# Shift_register_shematic.net
KiCad netlist of a schematic drawn in EAGLE
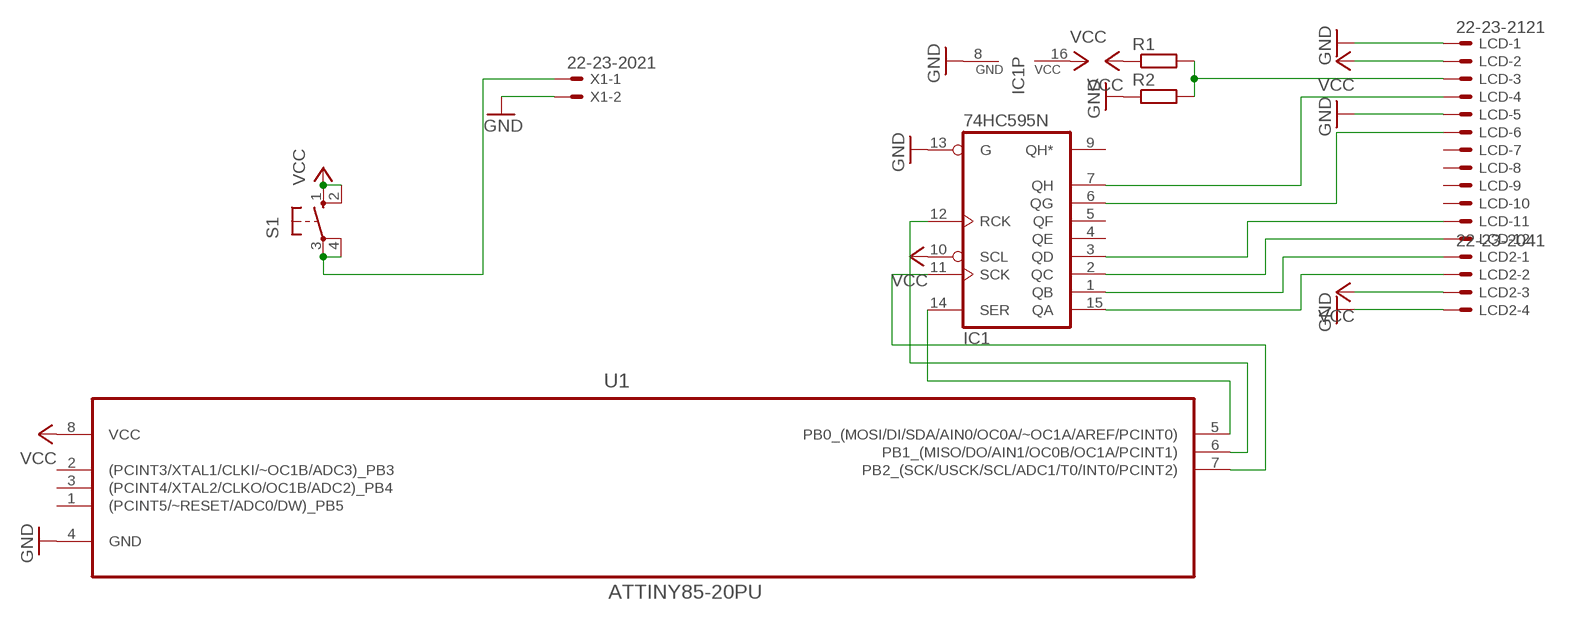
[diagram p0: schematic, sheet 1]

(export (version "E")
  (design (tool "Eeschema 10.0.6"))
  (components
    (comp (ref "IC1")
      (value "74HC595N")
      (footprint "eagle-import:DIL16")
      (libsource (lib "eagle-import") (part "74595NHC"))
    )
    (comp (ref "LCD")
      (value "22-23-2121")
      (footprint "eagle-import:22-23-2121")
      (fields (field (name "MF") "MOLEX"))
      (libsource (lib "eagle-import") (part "22-23-2121"))
    )
    (comp (ref "LCD2")
      (value "22-23-2041")
      (footprint "eagle-import:22-23-2041")
      (fields (field (name "MF") "MOLEX"))
      (libsource (lib "eagle-import") (part "22-23-2041"))
    )
    (comp (ref "R1")
      (value "R-EU_0207/10")
      (footprint "eagle-import:0207_10")
      (libsource (lib "eagle-import") (part "R-EU_0207/10"))
    )
    (comp (ref "R2")
      (value "R-EU_0207/10")
      (footprint "eagle-import:0207_10")
      (libsource (lib "eagle-import") (part "R-EU_0207/10"))
    )
    (comp (ref "S1")
      (value "40-XX")
      (footprint "eagle-import:B3F-40XX")
      (fields (field (name "MF") "OMRON COMPONENTS USA") (field (name "MPN") "B3F-4000"))
      (libsource (lib "eagle-import") (part "40-XX"))
    )
    (comp (ref "U1")
      (value "ATTINY85-20PU")
      (footprint "eagle-import:DIP254P762X533-8")
      (libsource (lib "eagle-import") (part "ATTINY85-20PU"))
    )
    (comp (ref "X1")
      (value "22-23-2021")
      (footprint "eagle-import:22-23-2021")
      (fields (field (name "MF") "MOLEX"))
      (libsource (lib "eagle-import") (part "22-23-2021"))
    )
  )
  (nets
    (net (code "1") (name "GND") (class "Default")
      (node (ref "IC1") (pin "13") (pinfunction "G_13") (pintype "input"))
      (node (ref "IC1") (pin "8") (pinfunction "GND_8") (pintype "power_in"))
      (node (ref "LCD") (pin "1") (pinfunction "S_1") (pintype "passive"))
      (node (ref "LCD") (pin "5") (pinfunction "S_5") (pintype "passive"))
      (node (ref "LCD2") (pin "4") (pinfunction "S_4") (pintype "passive"))
      (node (ref "R2") (pin "1") (pinfunction "1_1") (pintype "passive"))
      (node (ref "U1") (pin "4") (pinfunction "GND_4") (pintype "passive"))
      (node (ref "X1") (pin "2") (pinfunction "S_2") (pintype "passive"))
    )
    (net (code "2") (name "Net-(IC1A-QA)") (class "Default")
      (node (ref "IC1") (pin "15") (pinfunction "QA_15") (pintype "tri_state"))
      (node (ref "LCD2") (pin "2") (pinfunction "S_2") (pintype "passive"))
    )
    (net (code "3") (name "Net-(IC1A-QB)") (class "Default")
      (node (ref "IC1") (pin "1") (pinfunction "QB_1") (pintype "tri_state"))
      (node (ref "LCD2") (pin "1") (pinfunction "S_1") (pintype "passive"))
    )
    (net (code "4") (name "Net-(IC1A-QC)") (class "Default")
      (node (ref "IC1") (pin "2") (pinfunction "QC_2") (pintype "tri_state"))
      (node (ref "LCD") (pin "12") (pinfunction "S_12") (pintype "passive"))
    )
    (net (code "5") (name "Net-(IC1A-QD)") (class "Default")
      (node (ref "IC1") (pin "3") (pinfunction "QD_3") (pintype "tri_state"))
      (node (ref "LCD") (pin "11") (pinfunction "S_11") (pintype "passive"))
    )
    (net (code "6") (name "Net-(IC1A-QG)") (class "Default")
      (node (ref "IC1") (pin "6") (pinfunction "QG_6") (pintype "tri_state"))
      (node (ref "LCD") (pin "6") (pinfunction "S_6") (pintype "passive"))
    )
    (net (code "7") (name "Net-(IC1A-QH)") (class "Default")
      (node (ref "IC1") (pin "7") (pinfunction "QH_7") (pintype "tri_state"))
      (node (ref "LCD") (pin "4") (pinfunction "S_4") (pintype "passive"))
    )
    (net (code "8") (name "Net-(IC1A-RCK)") (class "Default")
      (node (ref "IC1") (pin "12") (pinfunction "RCK_12") (pintype "input"))
      (node (ref "U1") (pin "6") (pinfunction "PB1_(MISO/DO/AIN1/OC0B/OC1A/PCINT1)_6") (pintype "bidirectional"))
    )
    (net (code "9") (name "Net-(IC1A-SCK)") (class "Default")
      (node (ref "IC1") (pin "11") (pinfunction "SCK_11") (pintype "input"))
      (node (ref "U1") (pin "7") (pinfunction "PB2_(SCK/USCK/SCL/ADC1/T0/INT0/PCINT2)_7") (pintype "bidirectional"))
    )
    (net (code "10") (name "Net-(IC1A-SER)") (class "Default")
      (node (ref "IC1") (pin "14") (pinfunction "SER_14") (pintype "input"))
      (node (ref "U1") (pin "5") (pinfunction "PB0_(MOSI/DI/SDA/AIN0/OC0A/~{OC1A/AREF/PCINT0})_5") (pintype "bidirectional"))
    )
    (net (code "11") (name "Net-(LCDF-S)") (class "Default")
      (node (ref "LCD") (pin "3") (pinfunction "S_3") (pintype "passive"))
      (node (ref "R1") (pin "2") (pinfunction "2_2") (pintype "passive"))
      (node (ref "R2") (pin "2") (pinfunction "2_2") (pintype "passive"))
    )
    (net (code "12") (name "Net-(S1-P)") (class "Default")
      (node (ref "S1") (pin "3") (pinfunction "P_3") (pintype "passive"))
      (node (ref "S1") (pin "4") (pinfunction "P1_4") (pintype "passive"))
      (node (ref "X1") (pin "1") (pinfunction "S_1") (pintype "passive"))
    )
    (net (code "13") (name "VCC") (class "Default")
      (node (ref "IC1") (pin "10") (pinfunction "SCL_10") (pintype "input"))
      (node (ref "IC1") (pin "16") (pinfunction "VCC_16") (pintype "power_in"))
      (node (ref "LCD") (pin "2") (pinfunction "S_2") (pintype "passive"))
      (node (ref "LCD2") (pin "3") (pinfunction "S_3") (pintype "passive"))
      (node (ref "R1") (pin "1") (pinfunction "1_1") (pintype "passive"))
      (node (ref "S1") (pin "1") (pinfunction "S_1") (pintype "passive"))
      (node (ref "S1") (pin "2") (pinfunction "S1_2") (pintype "passive"))
      (node (ref "U1") (pin "8") (pinfunction "VCC_8") (pintype "power_in"))
    )
    (net (code "14") (name "unconnected-(IC1A-QE-Pad4)") (class "Default")
      (node (ref "IC1") (pin "4") (pinfunction "QE_4") (pintype "tri_state"))
    )
    (net (code "15") (name "unconnected-(IC1A-QF-Pad5)") (class "Default")
      (node (ref "IC1") (pin "5") (pinfunction "QF_5") (pintype "tri_state"))
    )
    (net (code "16") (name "unconnected-(IC1A-QH*-Pad9)") (class "Default")
      (node (ref "IC1") (pin "9") (pinfunction "QH*_9") (pintype "tri_state"))
    )
    (net (code "17") (name "unconnected-(LCDB-S-Pad10)") (class "Default")
      (node (ref "LCD") (pin "10") (pinfunction "S_10") (pintype "passive"))
    )
    (net (code "18") (name "unconnected-(LCDJ-S-Pad7)") (class "Default")
      (node (ref "LCD") (pin "7") (pinfunction "S_7") (pintype "passive"))
    )
    (net (code "19") (name "unconnected-(LCDK-S-Pad8)") (class "Default")
      (node (ref "LCD") (pin "8") (pinfunction "S_8") (pintype "passive"))
    )
    (net (code "20") (name "unconnected-(LCDL-S-Pad9)") (class "Default")
      (node (ref "LCD") (pin "9") (pinfunction "S_9") (pintype "passive"))
    )
    (net (code "21") (name "unconnected-(U1-(PCINT3{slash}XTAL1{slash}CLKI{slash}~{OC1B{slash}ADC3})_PB3-Pad2)") (class "Default")
      (node (ref "U1") (pin "2") (pinfunction "(PCINT3/XTAL1/CLKI/~{OC1B/ADC3})_PB3_2") (pintype "bidirectional"))
    )
    (net (code "22") (name "unconnected-(U1-(PCINT4{slash}XTAL2{slash}CLKO{slash}OC1B{slash}ADC2)_PB4-Pad3)") (class "Default")
      (node (ref "U1") (pin "3") (pinfunction "(PCINT4/XTAL2/CLKO/OC1B/ADC2)_PB4_3") (pintype "bidirectional"))
    )
    (net (code "23") (name "unconnected-(U1-(PCINT5{slash}~{RESET{slash}ADC0{slash}DW})_PB5-Pad1)") (class "Default")
      (node (ref "U1") (pin "1") (pinfunction "(PCINT5/~{RESET/ADC0/DW})_PB5_1") (pintype "bidirectional"))
    )
  )
)
